# ESP32.net
KiCad netlist of a schematic drawn in Altium Designer
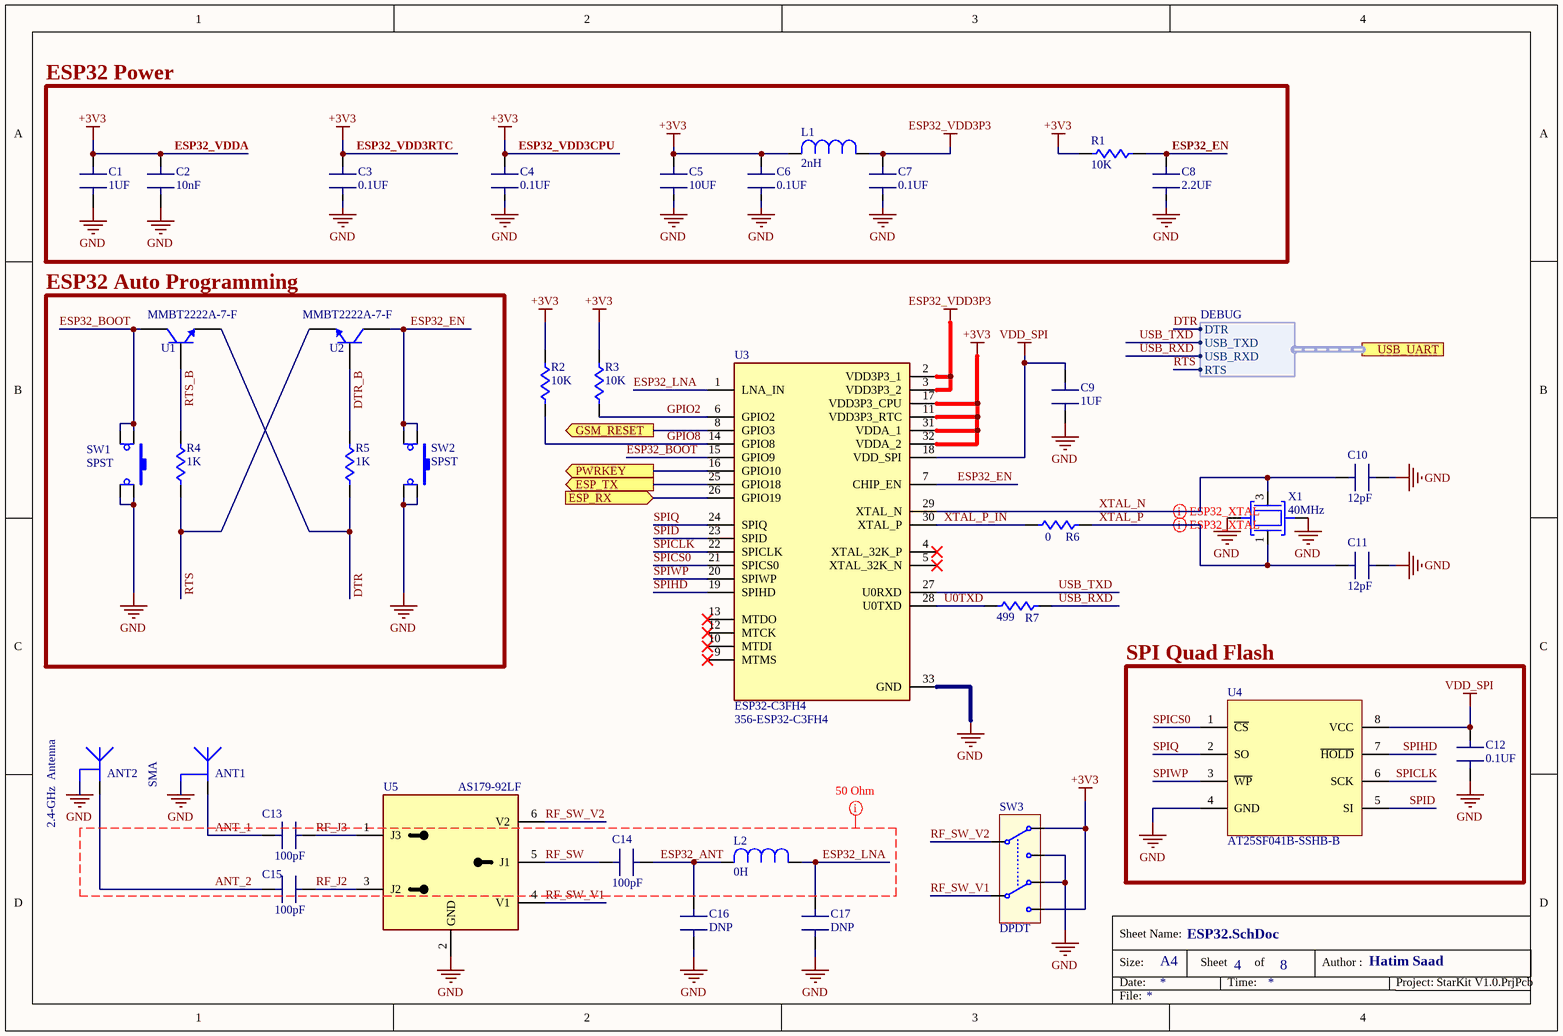
[diagram p0: ESP32.SchDoc]

(export (version "E")
  (design (tool "Eeschema 10.0.6"))
  (components
    (comp (ref "ANT1")
      (value "SMA")
      (footprint "SMA RIGHT DIGIKEY")
      (description "Right Angled Female SMA Connector")
      (libsource (lib "HZSchLib") (part "SMA_1"))
    )
    (comp (ref "ANT2")
      (value "2.4-GHz  Antenna")
      (footprint "ANT_2.4_AN043")
      (libsource (lib "HZSchLib") (part "ANT_2.4_AN043"))
    )
    (comp (ref "C1")
      (value "1UF")
      (footprint "CAP: 0603")
      (description "CAP SMD 0603")
      (libsource (lib "HZSchLib") (part "CAP 0603"))
    )
    (comp (ref "C2")
      (value "10nF")
      (footprint "CAP: 0603")
      (description "CAP SMD 0603")
      (libsource (lib "HZSchLib") (part "CAP 0603"))
    )
    (comp (ref "C3")
      (value "0.1UF")
      (footprint "CAP: 0603")
      (description "CAP SMD 0603")
      (libsource (lib "HZSchLib") (part "CAP 0603"))
    )
    (comp (ref "C4")
      (value "0.1UF")
      (footprint "CAP: 0603")
      (description "CAP SMD 0603")
      (libsource (lib "HZSchLib") (part "CAP 0603"))
    )
    (comp (ref "C5")
      (value "10UF")
      (footprint "CAP: 0805")
      (description "CAP SMD 0805")
      (libsource (lib "HZSchLib") (part "CAP 0805"))
    )
    (comp (ref "C6")
      (value "0.1UF")
      (footprint "CAP: 0603")
      (description "CAP SMD 0603")
      (libsource (lib "HZSchLib") (part "CAP 0603"))
    )
    (comp (ref "C7")
      (value "0.1UF")
      (footprint "CAP: 0603")
      (description "CAP SMD 0603")
      (libsource (lib "HZSchLib") (part "CAP 0603"))
    )
    (comp (ref "C8")
      (value "2.2UF")
      (footprint "CAP: 0603")
      (description "CAP SMD 0603")
      (libsource (lib "HZSchLib") (part "CAP 0603"))
    )
    (comp (ref "C9")
      (value "1UF")
      (footprint "CAP: 0603")
      (description "CAP SMD 0603")
      (libsource (lib "HZSchLib") (part "CAP 0603"))
    )
    (comp (ref "C10")
      (value "12pF")
      (footprint "CAP: 0603")
      (description "CAP SMD 0603")
      (libsource (lib "HZSchLib") (part "CAP 0603"))
    )
    (comp (ref "C11")
      (value "12pF")
      (footprint "CAP: 0603")
      (description "CAP SMD 0603")
      (libsource (lib "HZSchLib") (part "CAP 0603"))
    )
    (comp (ref "C12")
      (value "0.1UF")
      (footprint "CAP: 0603")
      (description "CAP SMD 0603")
      (libsource (lib "HZSchLib") (part "CAP 0603"))
    )
    (comp (ref "C13")
      (value "100pF")
      (footprint "CAP: 0603")
      (description "CAP SMD 0603")
      (libsource (lib "HZSchLib") (part "CAP 0603"))
    )
    (comp (ref "C14")
      (value "100pF")
      (footprint "CAP: 0603")
      (description "CAP SMD 0603")
      (libsource (lib "HZSchLib") (part "CAP 0603"))
    )
    (comp (ref "C15")
      (value "100pF")
      (footprint "CAP: 0603")
      (description "CAP SMD 0603")
      (libsource (lib "HZSchLib") (part "CAP 0603"))
    )
    (comp (ref "C16")
      (value "DNP")
      (footprint "CAP: 0603")
      (description "CAP SMD 0603")
      (libsource (lib "HZSchLib") (part "CAP 0603"))
    )
    (comp (ref "C17")
      (value "DNP")
      (footprint "CAP: 0603")
      (description "CAP SMD 0603")
      (libsource (lib "HZSchLib") (part "CAP 0603"))
    )
    (comp (ref "L1")
      (value "2nH")
      (footprint "IND: 0603")
      (description "IND SMD 0603")
      (libsource (lib "HZSchLib") (part "IND 0603"))
    )
    (comp (ref "L2")
      (value "0H")
      (footprint "IND: 0603")
      (description "IND SMD 0603")
      (libsource (lib "HZSchLib") (part "IND 0603"))
    )
    (comp (ref "R1")
      (value "10K")
      (footprint "RES: 0603")
      (description "RES SMD 0603")
      (libsource (lib "HZSchLib") (part "RES 0603"))
    )
    (comp (ref "R2")
      (value "10K")
      (footprint "RES: 0603")
      (description "RES SMD 0603")
      (libsource (lib "HZSchLib") (part "RES 0603"))
    )
    (comp (ref "R3")
      (value "10K")
      (footprint "RES: 0603")
      (description "RES SMD 0603")
      (libsource (lib "HZSchLib") (part "RES 0603"))
    )
    (comp (ref "R4")
      (value "1K")
      (footprint "RES: 0603")
      (description "RES SMD 0603")
      (libsource (lib "HZSchLib") (part "RES 0603"))
    )
    (comp (ref "R5")
      (value "1K")
      (footprint "RES: 0603")
      (description "RES SMD 0603")
      (libsource (lib "HZSchLib") (part "RES 0603"))
    )
    (comp (ref "R6")
      (value "0")
      (footprint "RES: 0603")
      (description "RES SMD 0603")
      (libsource (lib "HZSchLib") (part "RES 0603"))
    )
    (comp (ref "R7")
      (value "499")
      (footprint "RES: 0603")
      (description "RES SMD 0603")
      (libsource (lib "HZSchLib") (part "RES 0603"))
    )
    (comp (ref "SW1")
      (value "SPST")
      (footprint "Tactile Switch RKC2SJF170SMTRLFS")
      (description "Switch Tactile OFF-MOM SPST-NO Button J-Lead 12VDC 100000Cycles 500gf SMD T/R")
      (fields
        (field (name "MANUFACTURER") "ITT C&K")
        (field (name "MANUFACTURER PART NUMBER") "RKC2SJF170SMTRLFS")
      )
      (libsource (lib "HZSchLib") (part "RKC2SJF170SMTRLFS"))
    )
    (comp (ref "SW2")
      (value "SPST")
      (footprint "Tactile Switch RKC2SJF170SMTRLFS")
      (description "Switch Tactile OFF-MOM SPST-NO Button J-Lead 12VDC 100000Cycles 500gf SMD T/R")
      (fields
        (field (name "MANUFACTURER") "ITT C&K")
        (field (name "MANUFACTURER PART NUMBER") "RKC2SJF170SMTRLFS")
      )
      (libsource (lib "HZSchLib") (part "RKC2SJF170SMTRLFS"))
    )
    (comp (ref "SW3")
      (value "DPDT")
      (footprint "DPDT SWITCH")
      (description "Swicth DPDT 0.1A 12V 10000 SMD Slide Switches")
      (libsource (lib "HZSchLib") (part "MST22D18G2 125"))
    )
    (comp (ref "U1")
      (value "MMBT2222A-7-F")
      (footprint "SOT23_3")
      (description "MMBT2222 Series NPN 350 mW 40 V 600 mA SMT Small Signal Transistor - SOT-23")
      (fields (field (name "MANUFACTURER") "Diodes") (field (name "VOLTAGE") "40V"))
      (libsource (lib "HZSchLib") (part "MMBT2222A-7-F"))
    )
    (comp (ref "U2")
      (value "MMBT2222A-7-F")
      (footprint "SOT23_3")
      (description "MMBT2222 Series NPN 350 mW 40 V 600 mA SMT Small Signal Transistor - SOT-23")
      (fields (field (name "MANUFACTURER") "Diodes") (field (name "VOLTAGE") "40V"))
      (libsource (lib "HZSchLib") (part "MMBT2222A-7-F"))
    )
    (comp (ref "U3")
      (value "ESP32-C3FH4")
      (footprint "QFN-32")
      (description "SoC 32-Bit RISC 160MHz Single Core 4MB 32-Pin QFN T/R")
      (fields
        (field (name "MANUFACTURER") "Espressif Systems")
        (field (name "SUPPLIER PART NUMBER 1") "356-ESP32-C3FH4")
      )
      (libsource (lib "HZSchLib") (part "ESP32-C3FH4"))
    )
    (comp (ref "U4")
      (value "AT25SF041B-SSHB-B")
      (footprint "8-SOIC")
      (description "NOR Flash Serial (SPI, Dual SPI, Quad SPI) 3.3V 4M-bit 512K x 8 7ns Tube")
      (fields (field (name "MANUFACTURER") "Renesas"))
      (libsource (lib "HZSchLib") (part "AT25SF041B-SSHB-B"))
    )
    (comp (ref "U5")
      (value "AS179-92LF")
      (footprint "SC70-6")
      (description "RF Switch SPDT 0.02MHz to 4GHz 20dB Automotive 6-Pin SC-88 T/R / IC SW SPDT DC-3GHZ GAAS SC70-6")
      (fields (field (name "MANUFACTURER") "Skyworks Solutions"))
      (libsource (lib "HZSchLib") (part "AS179-92LF"))
    )
    (comp (ref "X1")
      (value "40MHz")
      (footprint "4-SMD, No Lead ECS")
      (description "Crystal 40MHz 10pF 4-Pin SMD ECX-1637B2 T/R")
      (fields
        (field (name "MANUFACTURER") "ECS International")
        (field (name "MANUFACTURER PART NUMBER") "ECS-400-10-37B2-CKY-TR")
      )
      (libsource (lib "HZSchLib") (part "ECS-400-10-37B2-CKY-TR"))
    )
  )
  (nets
    (net (code "2") (name "+3V3") (class "Default")
      (node (ref "C1") (pin "1") (pinfunction "A_1") (pintype "passive"))
      (node (ref "C2") (pin "1") (pinfunction "A_1") (pintype "passive"))
      (node (ref "C3") (pin "1") (pinfunction "A_1") (pintype "passive"))
      (node (ref "C4") (pin "1") (pinfunction "A_1") (pintype "passive"))
      (node (ref "C5") (pin "2") (pinfunction "B_2") (pintype "passive"))
      (node (ref "C6") (pin "1") (pinfunction "A_1") (pintype "passive"))
      (node (ref "L1") (pin "1") (pinfunction "1_1") (pintype "passive"))
      (node (ref "R1") (pin "1") (pinfunction "1_1") (pintype "passive"))
      (node (ref "R2") (pin "2") (pinfunction "2_2") (pintype "passive"))
      (node (ref "R3") (pin "2") (pinfunction "2_2") (pintype "passive"))
      (node (ref "SW3") (pin "1") (pinfunction "B1_1") (pintype "passive"))
      (node (ref "SW3") (pin "6") (pinfunction "B2_6") (pintype "passive"))
      (node (ref "U3") (pin "11") (pinfunction "VDD3P3_RTC_11") (pintype "passive"))
      (node (ref "U3") (pin "17") (pinfunction "VDD3P3_CPU_17") (pintype "passive"))
      (node (ref "U3") (pin "31") (pinfunction "VDDA_1_31") (pintype "passive"))
      (node (ref "U3") (pin "32") (pinfunction "VDDA_2_32") (pintype "passive"))
    )
    (net (code "3") (name "/ANT_1") (class "Default")
      (node (ref "ANT1") (pin "1") (pinfunction "1_1") (pintype "passive"))
      (node (ref "C13") (pin "2") (pinfunction "B_2") (pintype "passive"))
    )
    (net (code "4") (name "/ANT_2") (class "Default")
      (node (ref "ANT2") (pin "1") (pinfunction "1_1") (pintype "passive"))
      (node (ref "C15") (pin "2") (pinfunction "B_2") (pintype "passive"))
    )
    (net (code "5") (name "/DTR") (class "Default")
      (node (ref "R5") (pin "2") (pinfunction "2_2") (pintype "passive"))
      (node (ref "U1") (pin "2") (pinfunction "E_2") (pintype "passive"))
    )
    (net (code "6") (name "/DTR_B") (class "Default")
      (node (ref "R5") (pin "1") (pinfunction "1_1") (pintype "passive"))
      (node (ref "U2") (pin "1") (pinfunction "B_1") (pintype "passive"))
    )
    (net (code "7") (name "/ESP32_ANT") (class "Default")
      (node (ref "C14") (pin "1") (pinfunction "A_1") (pintype "passive"))
      (node (ref "C16") (pin "1") (pinfunction "A_1") (pintype "passive"))
      (node (ref "L2") (pin "1") (pinfunction "1_1") (pintype "passive"))
    )
    (net (code "8") (name "/ESP32_BOOT") (class "Default")
      (node (ref "SW1") (pin "1") (pinfunction "1_1") (pintype "passive"))
      (node (ref "SW1") (pin "2") (pinfunction "2_2") (pintype "passive"))
      (node (ref "U1") (pin "3") (pinfunction "C_3") (pintype "passive"))
      (node (ref "U3") (pin "15") (pinfunction "GPIO9_15") (pintype "passive"))
    )
    (net (code "9") (name "/ESP32_EN") (class "Default")
      (node (ref "C8") (pin "1") (pinfunction "A_1") (pintype "passive"))
      (node (ref "R1") (pin "2") (pinfunction "2_2") (pintype "passive"))
      (node (ref "SW2") (pin "1") (pinfunction "1_1") (pintype "passive"))
      (node (ref "SW2") (pin "2") (pinfunction "2_2") (pintype "passive"))
      (node (ref "U2") (pin "3") (pinfunction "C_3") (pintype "passive"))
      (node (ref "U3") (pin "7") (pinfunction "CHIP_EN_7") (pintype "passive"))
    )
    (net (code "10") (name "/ESP32_LNA") (class "Default")
      (node (ref "C17") (pin "1") (pinfunction "A_1") (pintype "passive"))
      (node (ref "L2") (pin "2") (pinfunction "2_2") (pintype "passive"))
      (node (ref "U3") (pin "1") (pinfunction "LNA_IN_1") (pintype "passive"))
    )
    (net (code "11") (name "/ESP_RX") (class "Default")
      (node (ref "U3") (pin "26") (pinfunction "GPIO19_26") (pintype "passive"))
    )
    (net (code "12") (name "/ESP_TX") (class "Default")
      (node (ref "U3") (pin "25") (pinfunction "GPIO18_25") (pintype "passive"))
    )
    (net (code "13") (name "/GPIO2") (class "Default")
      (node (ref "R3") (pin "1") (pinfunction "1_1") (pintype "passive"))
      (node (ref "U3") (pin "6") (pinfunction "GPIO2_6") (pintype "passive"))
    )
    (net (code "14") (name "/GPIO8") (class "Default")
      (node (ref "R2") (pin "1") (pinfunction "1_1") (pintype "passive"))
      (node (ref "U3") (pin "14") (pinfunction "GPIO8_14") (pintype "passive"))
    )
    (net (code "15") (name "/GSM_RESET") (class "Default")
      (node (ref "U3") (pin "8") (pinfunction "GPIO3_8") (pintype "passive"))
    )
    (net (code "16") (name "/PWRKEY") (class "Default")
      (node (ref "U3") (pin "16") (pinfunction "GPIO10_16") (pintype "passive"))
    )
    (net (code "17") (name "/RF_J2") (class "Default")
      (node (ref "C15") (pin "1") (pinfunction "A_1") (pintype "passive"))
      (node (ref "U5") (pin "3") (pinfunction "J2_3") (pintype "passive"))
    )
    (net (code "18") (name "/RF_J3") (class "Default")
      (node (ref "C13") (pin "1") (pinfunction "A_1") (pintype "passive"))
      (node (ref "U5") (pin "1") (pinfunction "J3_1") (pintype "passive"))
    )
    (net (code "19") (name "/RF_SW") (class "Default")
      (node (ref "C14") (pin "2") (pinfunction "B_2") (pintype "passive"))
      (node (ref "U5") (pin "5") (pinfunction "J1_5") (pintype "passive"))
    )
    (net (code "20") (name "/RF_SW_V1") (class "Default")
      (node (ref "SW3") (pin "5") (pinfunction "COM2_5") (pintype "passive"))
      (node (ref "U5") (pin "4") (pinfunction "V1_4") (pintype "passive"))
    )
    (net (code "21") (name "/RF_SW_V2") (class "Default")
      (node (ref "SW3") (pin "2") (pinfunction "COM1_2") (pintype "passive"))
      (node (ref "U5") (pin "6") (pinfunction "V2_6") (pintype "passive"))
    )
    (net (code "22") (name "/RTS") (class "Default")
      (node (ref "R4") (pin "2") (pinfunction "2_2") (pintype "passive"))
      (node (ref "U2") (pin "2") (pinfunction "E_2") (pintype "passive"))
    )
    (net (code "23") (name "/RTS_B") (class "Default")
      (node (ref "R4") (pin "1") (pinfunction "1_1") (pintype "passive"))
      (node (ref "U1") (pin "1") (pinfunction "B_1") (pintype "passive"))
    )
    (net (code "24") (name "/SPICLK") (class "Default")
      (node (ref "U3") (pin "22") (pinfunction "SPICLK_22") (pintype "passive"))
      (node (ref "U4") (pin "6") (pinfunction "SCK_6") (pintype "passive"))
    )
    (net (code "25") (name "/SPICS0") (class "Default")
      (node (ref "U3") (pin "21") (pinfunction "SPICS0_21") (pintype "passive"))
      (node (ref "U4") (pin "1") (pinfunction "~{CS}_1") (pintype "passive"))
    )
    (net (code "26") (name "/SPID") (class "Default")
      (node (ref "U3") (pin "23") (pinfunction "SPID_23") (pintype "passive"))
      (node (ref "U4") (pin "5") (pinfunction "SI_5") (pintype "passive"))
    )
    (net (code "27") (name "/SPIHD") (class "Default")
      (node (ref "U3") (pin "19") (pinfunction "SPIHD_19") (pintype "passive"))
      (node (ref "U4") (pin "7") (pinfunction "~{HOLD}_7") (pintype "passive"))
    )
    (net (code "28") (name "/SPIQ") (class "Default")
      (node (ref "U3") (pin "24") (pinfunction "SPIQ_24") (pintype "passive"))
      (node (ref "U4") (pin "2") (pinfunction "SO_2") (pintype "passive"))
    )
    (net (code "29") (name "/SPIWP") (class "Default")
      (node (ref "U3") (pin "20") (pinfunction "SPIWP_20") (pintype "passive"))
      (node (ref "U4") (pin "3") (pinfunction "~{WP}_3") (pintype "passive"))
    )
    (net (code "30") (name "/U0TXD") (class "Default")
      (node (ref "R7") (pin "1") (pinfunction "1_1") (pintype "passive"))
      (node (ref "U3") (pin "28") (pinfunction "U0TXD_28") (pintype "passive"))
    )
    (net (code "31") (name "/USB_RXD") (class "Default")
      (node (ref "R7") (pin "2") (pinfunction "2_2") (pintype "passive"))
    )
    (net (code "32") (name "/USB_TXD") (class "Default")
      (node (ref "U3") (pin "27") (pinfunction "U0RXD_27") (pintype "passive"))
    )
    (net (code "33") (name "/XTAL_N") (class "Default")
      (node (ref "C10") (pin "2") (pinfunction "B_2") (pintype "passive"))
      (node (ref "U3") (pin "29") (pinfunction "XTAL_N_29") (pintype "passive"))
      (node (ref "X1") (pin "3") (pinfunction "3_3") (pintype "passive"))
    )
    (net (code "34") (name "/XTAL_P") (class "Default")
      (node (ref "C11") (pin "2") (pinfunction "B_2") (pintype "passive"))
      (node (ref "R6") (pin "2") (pinfunction "2_2") (pintype "passive"))
      (node (ref "X1") (pin "1") (pinfunction "1_1") (pintype "passive"))
    )
    (net (code "35") (name "/XTAL_P_IN") (class "Default")
      (node (ref "R6") (pin "1") (pinfunction "1_1") (pintype "passive"))
      (node (ref "U3") (pin "30") (pinfunction "XTAL_P_30") (pintype "passive"))
    )
    (net (code "37") (name "ESP32_VDD3P3") (class "Default")
      (node (ref "C7") (pin "1") (pinfunction "A_1") (pintype "passive"))
      (node (ref "L1") (pin "2") (pinfunction "2_2") (pintype "passive"))
      (node (ref "U3") (pin "2") (pinfunction "VDD3P3_1_2") (pintype "passive"))
      (node (ref "U3") (pin "3") (pinfunction "VDD3P3_2_3") (pintype "passive"))
    )
    (net (code "38") (name "GND") (class "Default")
      (node (ref "ANT1") (pin "2") (pinfunction "2_2") (pintype "passive"))
      (node (ref "ANT2") (pin "2") (pinfunction "2_2") (pintype "passive"))
      (node (ref "C1") (pin "2") (pinfunction "B_2") (pintype "passive"))
      (node (ref "C10") (pin "1") (pinfunction "A_1") (pintype "passive"))
      (node (ref "C11") (pin "1") (pinfunction "A_1") (pintype "passive"))
      (node (ref "C12") (pin "2") (pinfunction "B_2") (pintype "passive"))
      (node (ref "C16") (pin "2") (pinfunction "B_2") (pintype "passive"))
      (node (ref "C17") (pin "2") (pinfunction "B_2") (pintype "passive"))
      (node (ref "C2") (pin "2") (pinfunction "B_2") (pintype "passive"))
      (node (ref "C3") (pin "2") (pinfunction "B_2") (pintype "passive"))
      (node (ref "C4") (pin "2") (pinfunction "B_2") (pintype "passive"))
      (node (ref "C5") (pin "1") (pinfunction "A_1") (pintype "passive"))
      (node (ref "C6") (pin "2") (pinfunction "B_2") (pintype "passive"))
      (node (ref "C7") (pin "2") (pinfunction "B_2") (pintype "passive"))
      (node (ref "C8") (pin "2") (pinfunction "B_2") (pintype "passive"))
      (node (ref "C9") (pin "2") (pinfunction "B_2") (pintype "passive"))
      (node (ref "SW1") (pin "3") (pinfunction "3_3") (pintype "passive"))
      (node (ref "SW1") (pin "4") (pinfunction "4_4") (pintype "passive"))
      (node (ref "SW2") (pin "3") (pinfunction "3_3") (pintype "passive"))
      (node (ref "SW2") (pin "4") (pinfunction "4_4") (pintype "passive"))
      (node (ref "SW3") (pin "3") (pinfunction "A1_3") (pintype "passive"))
      (node (ref "SW3") (pin "4") (pinfunction "A2_4") (pintype "passive"))
      (node (ref "U3") (pin "33") (pinfunction "GND_33") (pintype "passive"))
      (node (ref "U4") (pin "4") (pinfunction "GND_4") (pintype "passive"))
      (node (ref "U5") (pin "2") (pinfunction "GND_2") (pintype "passive"))
      (node (ref "X1") (pin "2") (pinfunction "GND_2") (pintype "power_in"))
      (node (ref "X1") (pin "4") (pinfunction "GND_4") (pintype "power_in"))
    )
    (net (code "39") (name "VDD_SPI") (class "Default")
      (node (ref "C12") (pin "1") (pinfunction "A_1") (pintype "passive"))
      (node (ref "C9") (pin "1") (pinfunction "A_1") (pintype "passive"))
      (node (ref "U3") (pin "18") (pinfunction "VDD_SPI_18") (pintype "passive"))
      (node (ref "U4") (pin "8") (pinfunction "VCC_8") (pintype "passive"))
    )
    (net (code "40") (name "unconnected-(U3-MTCK-Pad12)") (class "Default")
      (node (ref "U3") (pin "12") (pinfunction "MTCK_12") (pintype "passive+no_connect"))
    )
    (net (code "41") (name "unconnected-(U3-MTDI-Pad10)") (class "Default")
      (node (ref "U3") (pin "10") (pinfunction "MTDI_10") (pintype "passive+no_connect"))
    )
    (net (code "42") (name "unconnected-(U3-MTDO-Pad13)") (class "Default")
      (node (ref "U3") (pin "13") (pinfunction "MTDO_13") (pintype "passive+no_connect"))
    )
    (net (code "43") (name "unconnected-(U3-MTMS-Pad9)") (class "Default")
      (node (ref "U3") (pin "9") (pinfunction "MTMS_9") (pintype "passive+no_connect"))
    )
    (net (code "44") (name "unconnected-(U3-XTAL_32K_N-Pad5)") (class "Default")
      (node (ref "U3") (pin "5") (pinfunction "XTAL_32K_N_5") (pintype "passive+no_connect"))
    )
    (net (code "45") (name "unconnected-(U3-XTAL_32K_P-Pad4)") (class "Default")
      (node (ref "U3") (pin "4") (pinfunction "XTAL_32K_P_4") (pintype "passive+no_connect"))
    )
  )
)
